# boardPower.net
KiCad netlist of a schematic drawn in Altium Designer
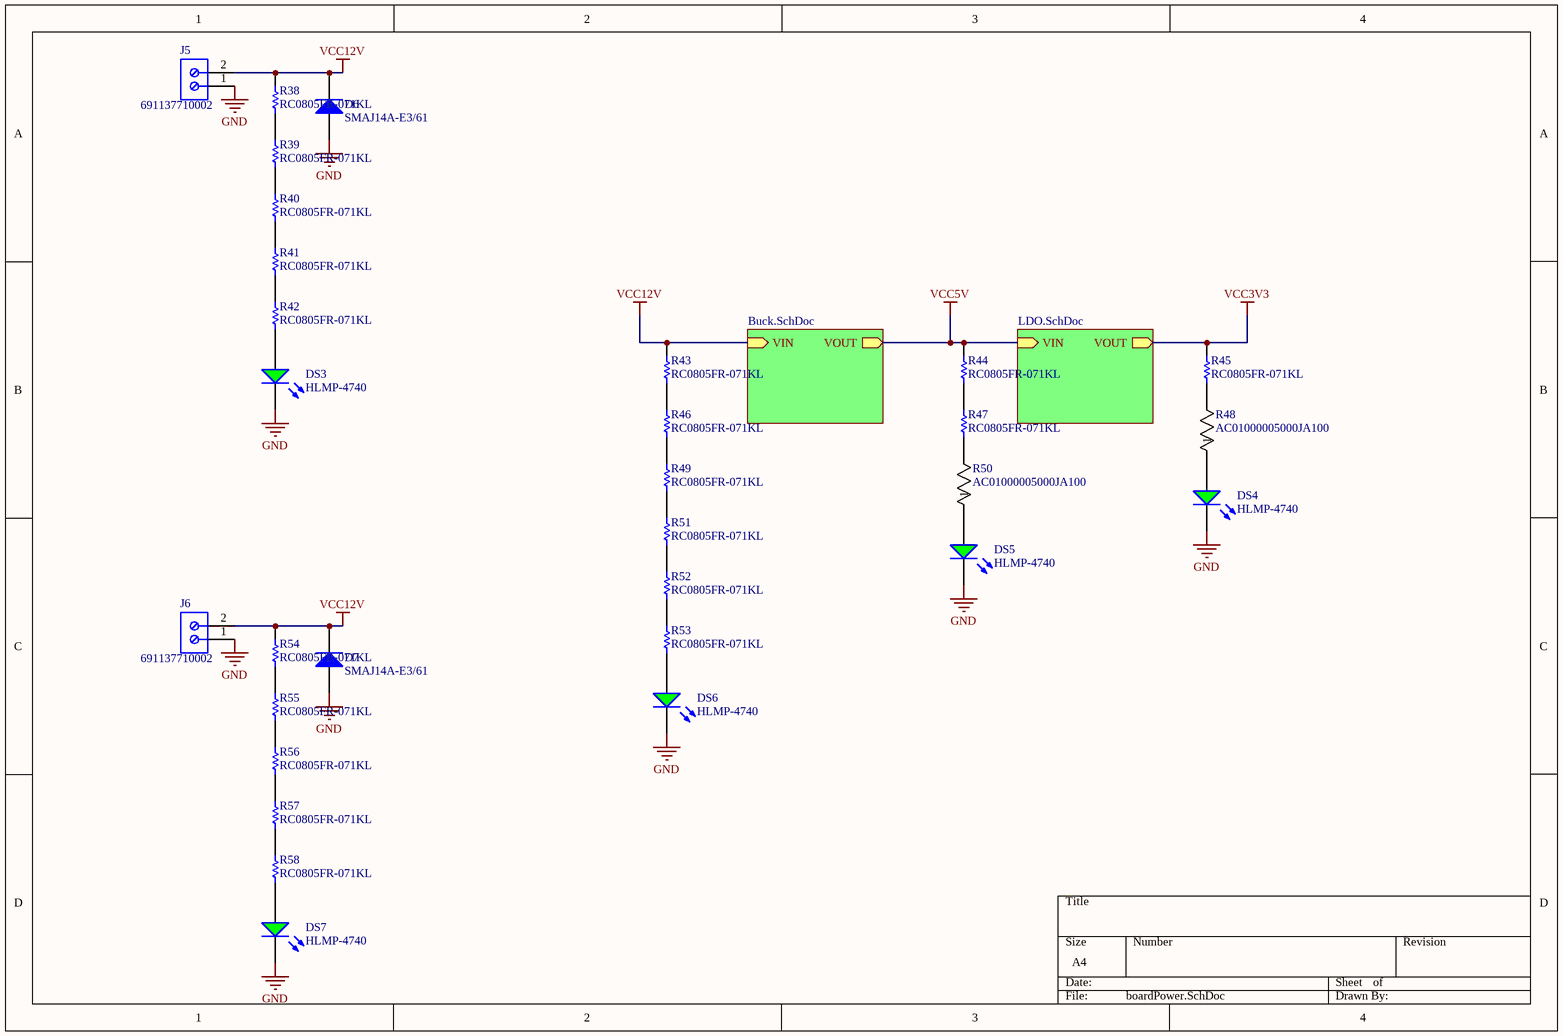
[diagram p0: boardPower.SchDoc]

(export (version "E")
  (design (tool "Eeschema 10.0.6"))
  (components
    (comp (ref "D6")
      (value "SMAJ14A-E3/61")
      (footprint "VISH-DO-214AC-2_L")
      (fields (field (name "MANUFACTURER") "Vishay Semiconductor"))
      (libsource (lib "Altium Content Vault") (part "VISH-K1A2-2"))
    )
    (comp (ref "D7")
      (value "SMAJ14A-E3/61")
      (footprint "VISH-DO-214AC-2_L")
      (fields (field (name "MANUFACTURER") "Vishay Semiconductor"))
      (libsource (lib "Altium Content Vault") (part "VISH-K1A2-2"))
    )
    (comp (ref "DS3")
      (value "HLMP-4740")
      (footprint "AVAG-HLMP-4740")
      (description "T-1 3/4 (5 mm) Low Current LED Lamp, Green, 1.9 V, -20 to 100 degC, 2-Pin THD, RoHS, Bulk")
      (fields (field (name "MANUFACTURER") "AvagoTechnologies"))
      (libsource (lib "Altium Content Vault") (part "LED-GREEN-AK-2"))
    )
    (comp (ref "DS4")
      (value "HLMP-4740")
      (footprint "AVAG-HLMP-4740")
      (description "T-1 3/4 (5 mm) Low Current LED Lamp, Green, 1.9 V, -20 to 100 degC, 2-Pin THD, RoHS, Bulk")
      (fields (field (name "MANUFACTURER") "AvagoTechnologies"))
      (libsource (lib "Altium Content Vault") (part "LED-GREEN-AK-2"))
    )
    (comp (ref "DS5")
      (value "HLMP-4740")
      (footprint "AVAG-HLMP-4740")
      (description "T-1 3/4 (5 mm) Low Current LED Lamp, Green, 1.9 V, -20 to 100 degC, 2-Pin THD, RoHS, Bulk")
      (fields (field (name "MANUFACTURER") "AvagoTechnologies"))
      (libsource (lib "Altium Content Vault") (part "LED-GREEN-AK-2"))
    )
    (comp (ref "DS6")
      (value "HLMP-4740")
      (footprint "AVAG-HLMP-4740")
      (description "T-1 3/4 (5 mm) Low Current LED Lamp, Green, 1.9 V, -20 to 100 degC, 2-Pin THD, RoHS, Bulk")
      (fields (field (name "MANUFACTURER") "AvagoTechnologies"))
      (libsource (lib "Altium Content Vault") (part "LED-GREEN-AK-2"))
    )
    (comp (ref "DS7")
      (value "HLMP-4740")
      (footprint "AVAG-HLMP-4740")
      (description "T-1 3/4 (5 mm) Low Current LED Lamp, Green, 1.9 V, -20 to 100 degC, 2-Pin THD, RoHS, Bulk")
      (fields (field (name "MANUFACTURER") "AvagoTechnologies"))
      (libsource (lib "Altium Content Vault") (part "LED-GREEN-AK-2"))
    )
    (comp (ref "J5")
      (value "691137710002")
      (footprint "691137710002")
      (libsource (lib "Altium Content Vault") (part "TBL - 1R - 02P - Screw"))
    )
    (comp (ref "J6")
      (value "691137710002")
      (footprint "691137710002")
      (libsource (lib "Altium Content Vault") (part "TBL - 1R - 02P - Screw"))
    )
    (comp (ref "R38")
      (value "RC0805FR-071KL")
      (footprint "RESC2013X60X35ML10T20")
      (description "Chip Resistor, 1 KOhm, +/- 1%, 125 mW, -55 to 155 degC, 0805 (2012 Metric), RoHS, Tape and Reel")
      (fields (field (name "TOLERANCE") "1%") (field (name "MANUFACTURER") "Yageo"))
      (libsource (lib "Altium Content Vault") (part "RES-2"))
    )
    (comp (ref "R39")
      (value "RC0805FR-071KL")
      (footprint "RESC2013X60X35ML10T20")
      (description "Chip Resistor, 1 KOhm, +/- 1%, 125 mW, -55 to 155 degC, 0805 (2012 Metric), RoHS, Tape and Reel")
      (fields (field (name "TOLERANCE") "1%") (field (name "MANUFACTURER") "Yageo"))
      (libsource (lib "Altium Content Vault") (part "RES-2"))
    )
    (comp (ref "R40")
      (value "RC0805FR-071KL")
      (footprint "RESC2013X60X35ML10T20")
      (description "Chip Resistor, 1 KOhm, +/- 1%, 125 mW, -55 to 155 degC, 0805 (2012 Metric), RoHS, Tape and Reel")
      (fields (field (name "TOLERANCE") "1%") (field (name "MANUFACTURER") "Yageo"))
      (libsource (lib "Altium Content Vault") (part "RES-2"))
    )
    (comp (ref "R41")
      (value "RC0805FR-071KL")
      (footprint "RESC2013X60X35ML10T20")
      (description "Chip Resistor, 1 KOhm, +/- 1%, 125 mW, -55 to 155 degC, 0805 (2012 Metric), RoHS, Tape and Reel")
      (fields (field (name "TOLERANCE") "1%") (field (name "MANUFACTURER") "Yageo"))
      (libsource (lib "Altium Content Vault") (part "RES-2"))
    )
    (comp (ref "R42")
      (value "RC0805FR-071KL")
      (footprint "RESC2013X60X35ML10T20")
      (description "Chip Resistor, 1 KOhm, +/- 1%, 125 mW, -55 to 155 degC, 0805 (2012 Metric), RoHS, Tape and Reel")
      (fields (field (name "TOLERANCE") "1%") (field (name "MANUFACTURER") "Yageo"))
      (libsource (lib "Altium Content Vault") (part "RES-2"))
    )
    (comp (ref "R43")
      (value "RC0805FR-071KL")
      (footprint "RESC2013X60X35ML10T20")
      (description "Chip Resistor, 1 KOhm, +/- 1%, 125 mW, -55 to 155 degC, 0805 (2012 Metric), RoHS, Tape and Reel")
      (fields (field (name "TOLERANCE") "1%") (field (name "MANUFACTURER") "Yageo"))
      (libsource (lib "Altium Content Vault") (part "RES-2"))
    )
    (comp (ref "R44")
      (value "RC0805FR-071KL")
      (footprint "RESC2013X60X35ML10T20")
      (description "Chip Resistor, 1 KOhm, +/- 1%, 125 mW, -55 to 155 degC, 0805 (2012 Metric), RoHS, Tape and Reel")
      (fields (field (name "TOLERANCE") "1%") (field (name "MANUFACTURER") "Yageo"))
      (libsource (lib "Altium Content Vault") (part "RES-2"))
    )
    (comp (ref "R45")
      (value "RC0805FR-071KL")
      (footprint "RESC2013X60X35ML10T20")
      (description "Chip Resistor, 1 KOhm, +/- 1%, 125 mW, -55 to 155 degC, 0805 (2012 Metric), RoHS, Tape and Reel")
      (fields (field (name "TOLERANCE") "1%") (field (name "MANUFACTURER") "Yageo"))
      (libsource (lib "Altium Content Vault") (part "RES-2"))
    )
    (comp (ref "R46")
      (value "RC0805FR-071KL")
      (footprint "RESC2013X60X35ML10T20")
      (description "Chip Resistor, 1 KOhm, +/- 1%, 125 mW, -55 to 155 degC, 0805 (2012 Metric), RoHS, Tape and Reel")
      (fields (field (name "TOLERANCE") "1%") (field (name "MANUFACTURER") "Yageo"))
      (libsource (lib "Altium Content Vault") (part "RES-2"))
    )
    (comp (ref "R47")
      (value "RC0805FR-071KL")
      (footprint "RESC2013X60X35ML10T20")
      (description "Chip Resistor, 1 KOhm, +/- 1%, 125 mW, -55 to 155 degC, 0805 (2012 Metric), RoHS, Tape and Reel")
      (fields (field (name "TOLERANCE") "1%") (field (name "MANUFACTURER") "Yageo"))
      (libsource (lib "Altium Content Vault") (part "RES-2"))
    )
    (comp (ref "R48")
      (value "AC01000005000JA100")
      (footprint "RES_AC01_VIS")
      (fields (field (name "TOLERANCE") "5%"))
      (libsource (lib "Altium Content Vault") (part "AC01000005000JA100"))
    )
    (comp (ref "R49")
      (value "RC0805FR-071KL")
      (footprint "RESC2013X60X35ML10T20")
      (description "Chip Resistor, 1 KOhm, +/- 1%, 125 mW, -55 to 155 degC, 0805 (2012 Metric), RoHS, Tape and Reel")
      (fields (field (name "TOLERANCE") "1%") (field (name "MANUFACTURER") "Yageo"))
      (libsource (lib "Altium Content Vault") (part "RES-2"))
    )
    (comp (ref "R50")
      (value "AC01000005000JA100")
      (footprint "RES_AC01_VIS")
      (fields (field (name "TOLERANCE") "5%"))
      (libsource (lib "Altium Content Vault") (part "AC01000005000JA100"))
    )
    (comp (ref "R51")
      (value "RC0805FR-071KL")
      (footprint "RESC2013X60X35ML10T20")
      (description "Chip Resistor, 1 KOhm, +/- 1%, 125 mW, -55 to 155 degC, 0805 (2012 Metric), RoHS, Tape and Reel")
      (fields (field (name "TOLERANCE") "1%") (field (name "MANUFACTURER") "Yageo"))
      (libsource (lib "Altium Content Vault") (part "RES-2"))
    )
    (comp (ref "R52")
      (value "RC0805FR-071KL")
      (footprint "RESC2013X60X35ML10T20")
      (description "Chip Resistor, 1 KOhm, +/- 1%, 125 mW, -55 to 155 degC, 0805 (2012 Metric), RoHS, Tape and Reel")
      (fields (field (name "TOLERANCE") "1%") (field (name "MANUFACTURER") "Yageo"))
      (libsource (lib "Altium Content Vault") (part "RES-2"))
    )
    (comp (ref "R53")
      (value "RC0805FR-071KL")
      (footprint "RESC2013X60X35ML10T20")
      (description "Chip Resistor, 1 KOhm, +/- 1%, 125 mW, -55 to 155 degC, 0805 (2012 Metric), RoHS, Tape and Reel")
      (fields (field (name "TOLERANCE") "1%") (field (name "MANUFACTURER") "Yageo"))
      (libsource (lib "Altium Content Vault") (part "RES-2"))
    )
    (comp (ref "R54")
      (value "RC0805FR-071KL")
      (footprint "RESC2013X60X35ML10T20")
      (description "Chip Resistor, 1 KOhm, +/- 1%, 125 mW, -55 to 155 degC, 0805 (2012 Metric), RoHS, Tape and Reel")
      (fields (field (name "TOLERANCE") "1%") (field (name "MANUFACTURER") "Yageo"))
      (libsource (lib "Altium Content Vault") (part "RES-2"))
    )
    (comp (ref "R55")
      (value "RC0805FR-071KL")
      (footprint "RESC2013X60X35ML10T20")
      (description "Chip Resistor, 1 KOhm, +/- 1%, 125 mW, -55 to 155 degC, 0805 (2012 Metric), RoHS, Tape and Reel")
      (fields (field (name "TOLERANCE") "1%") (field (name "MANUFACTURER") "Yageo"))
      (libsource (lib "Altium Content Vault") (part "RES-2"))
    )
    (comp (ref "R56")
      (value "RC0805FR-071KL")
      (footprint "RESC2013X60X35ML10T20")
      (description "Chip Resistor, 1 KOhm, +/- 1%, 125 mW, -55 to 155 degC, 0805 (2012 Metric), RoHS, Tape and Reel")
      (fields (field (name "TOLERANCE") "1%") (field (name "MANUFACTURER") "Yageo"))
      (libsource (lib "Altium Content Vault") (part "RES-2"))
    )
    (comp (ref "R57")
      (value "RC0805FR-071KL")
      (footprint "RESC2013X60X35ML10T20")
      (description "Chip Resistor, 1 KOhm, +/- 1%, 125 mW, -55 to 155 degC, 0805 (2012 Metric), RoHS, Tape and Reel")
      (fields (field (name "TOLERANCE") "1%") (field (name "MANUFACTURER") "Yageo"))
      (libsource (lib "Altium Content Vault") (part "RES-2"))
    )
    (comp (ref "R58")
      (value "RC0805FR-071KL")
      (footprint "RESC2013X60X35ML10T20")
      (description "Chip Resistor, 1 KOhm, +/- 1%, 125 mW, -55 to 155 degC, 0805 (2012 Metric), RoHS, Tape and Reel")
      (fields (field (name "TOLERANCE") "1%") (field (name "MANUFACTURER") "Yageo"))
      (libsource (lib "Altium Content Vault") (part "RES-2"))
    )
  )
  (nets
    (net (code "1") (name "GND") (class "Default")
      (node (ref "D6") (pin "2") (pinfunction "A_2") (pintype "passive"))
      (node (ref "D7") (pin "2") (pinfunction "A_2") (pintype "passive"))
      (node (ref "DS3") (pin "2") (pinfunction "K_2") (pintype "passive"))
      (node (ref "DS4") (pin "2") (pinfunction "K_2") (pintype "passive"))
      (node (ref "DS5") (pin "2") (pinfunction "K_2") (pintype "passive"))
      (node (ref "DS6") (pin "2") (pinfunction "K_2") (pintype "passive"))
      (node (ref "DS7") (pin "2") (pinfunction "K_2") (pintype "passive"))
      (node (ref "J5") (pin "1") (pinfunction "1_1") (pintype "passive"))
      (node (ref "J6") (pin "1") (pinfunction "1_1") (pintype "passive"))
    )
    (net (code "2") (name "Net-(DS3-A)") (class "Default")
      (node (ref "DS3") (pin "1") (pinfunction "A_1") (pintype "passive"))
      (node (ref "R42") (pin "1") (pinfunction "1_1") (pintype "passive"))
    )
    (net (code "3") (name "Net-(DS4-A)") (class "Default")
      (node (ref "DS4") (pin "1") (pinfunction "A_1") (pintype "passive"))
      (node (ref "R48") (pin "1") (pinfunction "1_1") (pintype "passive"))
    )
    (net (code "4") (name "Net-(DS5-A)") (class "Default")
      (node (ref "DS5") (pin "1") (pinfunction "A_1") (pintype "passive"))
      (node (ref "R50") (pin "1") (pinfunction "1_1") (pintype "passive"))
    )
    (net (code "5") (name "Net-(DS6-A)") (class "Default")
      (node (ref "DS6") (pin "1") (pinfunction "A_1") (pintype "passive"))
      (node (ref "R53") (pin "1") (pinfunction "1_1") (pintype "passive"))
    )
    (net (code "6") (name "Net-(DS7-A)") (class "Default")
      (node (ref "DS7") (pin "1") (pinfunction "A_1") (pintype "passive"))
      (node (ref "R58") (pin "1") (pinfunction "1_1") (pintype "passive"))
    )
    (net (code "7") (name "Net-(R38-Pad1)") (class "Default")
      (node (ref "R38") (pin "1") (pinfunction "1_1") (pintype "passive"))
      (node (ref "R39") (pin "2") (pinfunction "2_2") (pintype "passive"))
    )
    (net (code "8") (name "Net-(R39-Pad1)") (class "Default")
      (node (ref "R39") (pin "1") (pinfunction "1_1") (pintype "passive"))
      (node (ref "R40") (pin "2") (pinfunction "2_2") (pintype "passive"))
    )
    (net (code "9") (name "Net-(R40-Pad1)") (class "Default")
      (node (ref "R40") (pin "1") (pinfunction "1_1") (pintype "passive"))
      (node (ref "R41") (pin "2") (pinfunction "2_2") (pintype "passive"))
    )
    (net (code "10") (name "Net-(R41-Pad1)") (class "Default")
      (node (ref "R41") (pin "1") (pinfunction "1_1") (pintype "passive"))
      (node (ref "R42") (pin "2") (pinfunction "2_2") (pintype "passive"))
    )
    (net (code "11") (name "Net-(R43-Pad1)") (class "Default")
      (node (ref "R43") (pin "1") (pinfunction "1_1") (pintype "passive"))
      (node (ref "R46") (pin "2") (pinfunction "2_2") (pintype "passive"))
    )
    (net (code "12") (name "Net-(R44-Pad1)") (class "Default")
      (node (ref "R44") (pin "1") (pinfunction "1_1") (pintype "passive"))
      (node (ref "R47") (pin "2") (pinfunction "2_2") (pintype "passive"))
    )
    (net (code "13") (name "Net-(R45-Pad1)") (class "Default")
      (node (ref "R45") (pin "1") (pinfunction "1_1") (pintype "passive"))
      (node (ref "R48") (pin "2") (pinfunction "2_2") (pintype "passive"))
    )
    (net (code "14") (name "Net-(R46-Pad1)") (class "Default")
      (node (ref "R46") (pin "1") (pinfunction "1_1") (pintype "passive"))
      (node (ref "R49") (pin "2") (pinfunction "2_2") (pintype "passive"))
    )
    (net (code "15") (name "Net-(R47-Pad1)") (class "Default")
      (node (ref "R47") (pin "1") (pinfunction "1_1") (pintype "passive"))
      (node (ref "R50") (pin "2") (pinfunction "2_2") (pintype "passive"))
    )
    (net (code "16") (name "Net-(R49-Pad1)") (class "Default")
      (node (ref "R49") (pin "1") (pinfunction "1_1") (pintype "passive"))
      (node (ref "R51") (pin "2") (pinfunction "2_2") (pintype "passive"))
    )
    (net (code "17") (name "Net-(R51-Pad1)") (class "Default")
      (node (ref "R51") (pin "1") (pinfunction "1_1") (pintype "passive"))
      (node (ref "R52") (pin "2") (pinfunction "2_2") (pintype "passive"))
    )
    (net (code "18") (name "Net-(R52-Pad1)") (class "Default")
      (node (ref "R52") (pin "1") (pinfunction "1_1") (pintype "passive"))
      (node (ref "R53") (pin "2") (pinfunction "2_2") (pintype "passive"))
    )
    (net (code "19") (name "Net-(R54-Pad1)") (class "Default")
      (node (ref "R54") (pin "1") (pinfunction "1_1") (pintype "passive"))
      (node (ref "R55") (pin "2") (pinfunction "2_2") (pintype "passive"))
    )
    (net (code "20") (name "Net-(R55-Pad1)") (class "Default")
      (node (ref "R55") (pin "1") (pinfunction "1_1") (pintype "passive"))
      (node (ref "R56") (pin "2") (pinfunction "2_2") (pintype "passive"))
    )
    (net (code "21") (name "Net-(R56-Pad1)") (class "Default")
      (node (ref "R56") (pin "1") (pinfunction "1_1") (pintype "passive"))
      (node (ref "R57") (pin "2") (pinfunction "2_2") (pintype "passive"))
    )
    (net (code "22") (name "Net-(R57-Pad1)") (class "Default")
      (node (ref "R57") (pin "1") (pinfunction "1_1") (pintype "passive"))
      (node (ref "R58") (pin "2") (pinfunction "2_2") (pintype "passive"))
    )
    (net (code "23") (name "VCC3V3") (class "Default")
      (node (ref "R45") (pin "2") (pinfunction "2_2") (pintype "passive"))
    )
    (net (code "24") (name "VCC5V") (class "Default")
      (node (ref "R44") (pin "2") (pinfunction "2_2") (pintype "passive"))
    )
    (net (code "25") (name "VCC12V") (class "Default")
      (node (ref "D6") (pin "1") (pinfunction "K_1") (pintype "passive"))
      (node (ref "D7") (pin "1") (pinfunction "K_1") (pintype "passive"))
      (node (ref "J5") (pin "2") (pinfunction "2_2") (pintype "passive"))
      (node (ref "J6") (pin "2") (pinfunction "2_2") (pintype "passive"))
      (node (ref "R38") (pin "2") (pinfunction "2_2") (pintype "passive"))
      (node (ref "R43") (pin "2") (pinfunction "2_2") (pintype "passive"))
      (node (ref "R54") (pin "2") (pinfunction "2_2") (pintype "passive"))
    )
  )
)
